# Circuit_Needs_aproval.net
KiCad netlist of a schematic drawn in EAGLE
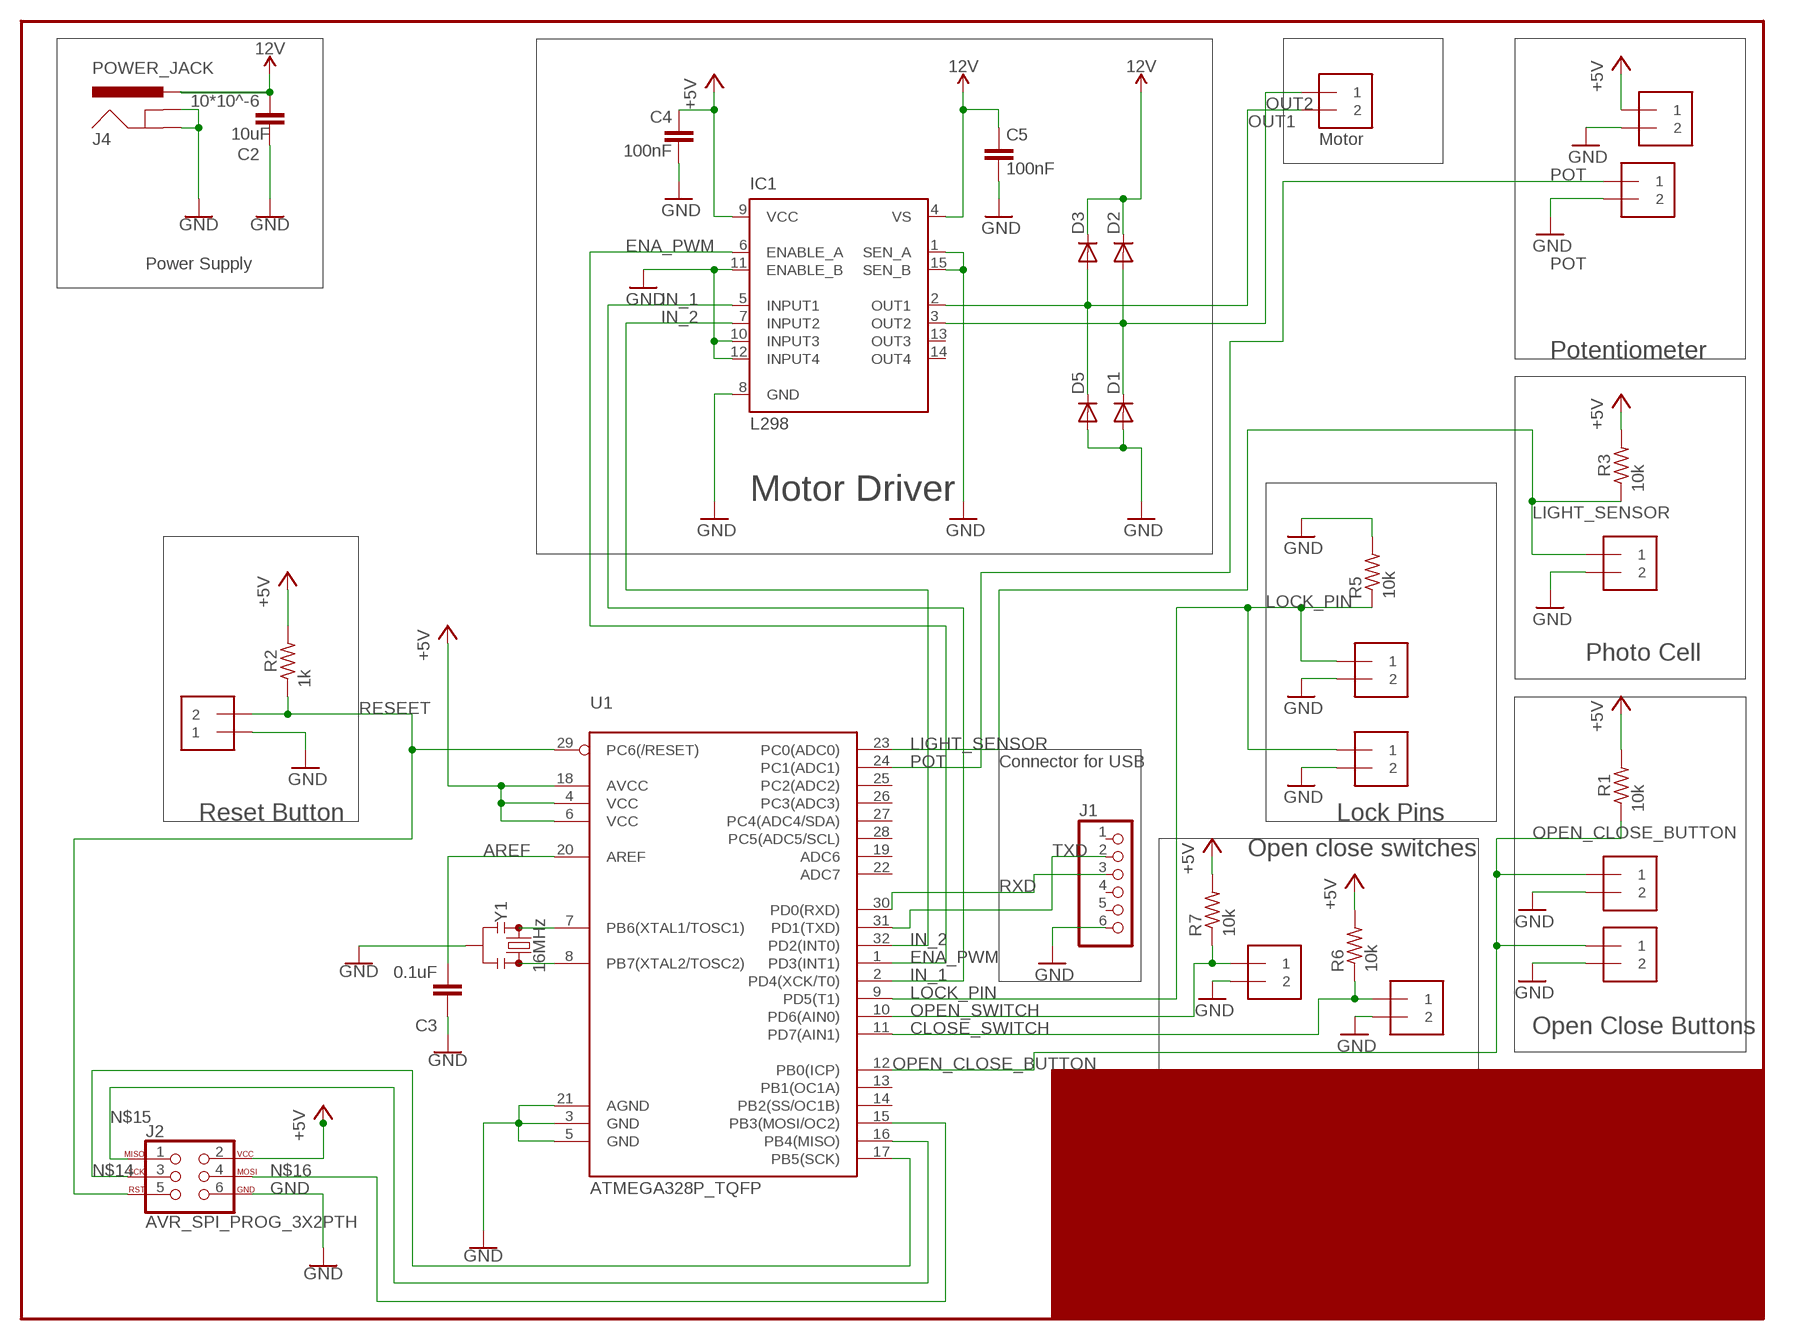
[diagram p0: schematic, sheet 1]

(export (version "E")
  (design (tool "Eeschema 10.0.6"))
  (components
    (comp (ref "C2")
      (value "10*10^-6")
      (footprint "eagle-import:C0805")
      (fields (field (name "SPICEPREFIX") "C") (field (name "SPICEPREFIX_1") "10uF"))
      (libsource (lib "eagle-import") (part "C-EUC0805"))
    )
    (comp (ref "C3")
      (value "0.1uF")
      (footprint "eagle-import:C0805")
      (libsource (lib "eagle-import") (part "C-EUC0805"))
    )
    (comp (ref "C4")
      (value "100nF")
      (footprint "eagle-import:C0805")
      (libsource (lib "eagle-import") (part "C-EUC0805"))
    )
    (comp (ref "C5")
      (value "100nF")
      (footprint "eagle-import:C0805")
      (libsource (lib "eagle-import") (part "C-EUC0805"))
    )
    (comp (ref "CLOSESWITCH")
      (value "1X2-3.5MM")
      (footprint "eagle-import:1X2-3.5MM")
      (libsource (lib "eagle-import") (part "1X2-3.5MM"))
    )
    (comp (ref "D1")
      (value "DIODE-DO214AA")
      (footprint "eagle-import:DO214AA")
      (libsource (lib "eagle-import") (part "DIODE-DO214AA"))
    )
    (comp (ref "D2")
      (value "DIODE-DO214AA")
      (footprint "eagle-import:DO214AA")
      (libsource (lib "eagle-import") (part "DIODE-DO214AA"))
    )
    (comp (ref "D3")
      (value "DIODE-DO214AA")
      (footprint "eagle-import:DO214AA")
      (libsource (lib "eagle-import") (part "DIODE-DO214AA"))
    )
    (comp (ref "D5")
      (value "DIODE-DO214AA")
      (footprint "eagle-import:DO214AA")
      (libsource (lib "eagle-import") (part "DIODE-DO214AA"))
    )
    (comp (ref "FRAME1")
      (value "FRAME-LETTER")
      (footprint "eagle-import:CREATIVE_COMMONS")
      (libsource (lib "eagle-import") (part "FRAME-LETTER"))
    )
    (comp (ref "IC1")
      (value "L298")
      (footprint "eagle-import:MULTIWATT-15")
      (fields (field (name "MPN") "L298N"))
      (libsource (lib "eagle-import") (part "L298"))
    )
    (comp (ref "INSIDE_BUTTON")
      (value "1X2-3.5MM")
      (footprint "eagle-import:1X2-3.5MM")
      (libsource (lib "eagle-import") (part "1X2-3.5MM"))
    )
    (comp (ref "J1")
      (value "PINHD-1X6")
      (footprint "eagle-import:1X06")
      (libsource (lib "eagle-import") (part "PINHD-1X6"))
    )
    (comp (ref "J2")
      (value "AVR_SPI_PROG_3X2PTH")
      (footprint "eagle-import:2X3")
      (libsource (lib "eagle-import") (part "AVR_SPI_PROG_3X2PTH"))
    )
    (comp (ref "J4")
      (value "POWER_JACK")
      (footprint "eagle-import:POWER_JACK_PTH")
      (libsource (lib "eagle-import") (part "POWER_JACK"))
    )
    (comp (ref "LIGHT_SENSOR")
      (value "1X2-3.5MM")
      (footprint "eagle-import:1X2-3.5MM")
      (libsource (lib "eagle-import") (part "1X2-3.5MM"))
    )
    (comp (ref "LOCK_PIN1")
      (value "1X2-3.5MM")
      (footprint "eagle-import:1X2-3.5MM")
      (libsource (lib "eagle-import") (part "1X2-3.5MM"))
    )
    (comp (ref "LOCK_PIN2")
      (value "1X2-3.5MM")
      (footprint "eagle-import:1X2-3.5MM")
      (libsource (lib "eagle-import") (part "1X2-3.5MM"))
    )
    (comp (ref "MOTOR")
      (value "1X2-3.5MM")
      (footprint "eagle-import:1X2-3.5MM")
      (libsource (lib "eagle-import") (part "1X2-3.5MM"))
    )
    (comp (ref "OUTSIDE_BUTTON")
      (value "1X2-3.5MM")
      (footprint "eagle-import:1X2-3.5MM")
      (libsource (lib "eagle-import") (part "1X2-3.5MM"))
    )
    (comp (ref "OUTSIDE_OPEN_BUTTON")
      (value "1X2-3.5MM")
      (footprint "eagle-import:1X2-3.5MM")
      (libsource (lib "eagle-import") (part "1X2-3.5MM"))
    )
    (comp (ref "POT")
      (value "1X2-3.5MM")
      (footprint "eagle-import:1X2-3.5MM")
      (libsource (lib "eagle-import") (part "1X2-3.5MM"))
    )
    (comp (ref "POTPOWER")
      (value "1X2-3.5MM")
      (footprint "eagle-import:1X2-3.5MM")
      (libsource (lib "eagle-import") (part "1X2-3.5MM"))
    )
    (comp (ref "R1")
      (value "10k")
      (footprint "eagle-import:M0805")
      (libsource (lib "eagle-import") (part "R-US_M0805"))
    )
    (comp (ref "R2")
      (value "1k")
      (footprint "eagle-import:M0805")
      (libsource (lib "eagle-import") (part "R-US_M0805"))
    )
    (comp (ref "R3")
      (value "10k")
      (footprint "eagle-import:M0805")
      (libsource (lib "eagle-import") (part "R-US_M0805"))
    )
    (comp (ref "R5")
      (value "10k")
      (footprint "eagle-import:M0805")
      (libsource (lib "eagle-import") (part "R-US_M0805"))
    )
    (comp (ref "R6")
      (value "10k")
      (footprint "eagle-import:M0805")
      (libsource (lib "eagle-import") (part "R-US_M0805"))
    )
    (comp (ref "R7")
      (value "10k")
      (footprint "eagle-import:M0805")
      (libsource (lib "eagle-import") (part "R-US_M0805"))
    )
    (comp (ref "RESETBUTTON")
      (value "1X2-3.5MM")
      (footprint "eagle-import:1X2-3.5MM")
      (libsource (lib "eagle-import") (part "1X2-3.5MM"))
    )
    (comp (ref "U1")
      (value "ATMEGA328P_TQFP")
      (footprint "eagle-import:TQFP32-08")
      (libsource (lib "eagle-import") (part "ATMEGA328P_TQFP"))
    )
    (comp (ref "Y1")
      (value "16MHz")
      (footprint "eagle-import:RESONATOR-SMD-3.2X1.3")
      (libsource (lib "eagle-import") (part "RESONATOR-16MHZSMD_3.2X1.3"))
    )
  )
  (nets
    (net (code "1") (name "+5V") (class "Default")
      (node (ref "C4") (pin "1") (pinfunction "1_1") (pintype "passive"))
      (node (ref "IC1") (pin "9") (pinfunction "VCC_9") (pintype "power_in"))
      (node (ref "J2") (pin "2") (pinfunction "2_2") (pintype "passive"))
      (node (ref "POTPOWER") (pin "1") (pinfunction "1_1") (pintype "passive"))
      (node (ref "R1") (pin "2") (pinfunction "2_2") (pintype "passive"))
      (node (ref "R2") (pin "2") (pinfunction "2_2") (pintype "passive"))
      (node (ref "R3") (pin "2") (pinfunction "2_2") (pintype "passive"))
      (node (ref "R6") (pin "2") (pinfunction "2_2") (pintype "passive"))
      (node (ref "R7") (pin "2") (pinfunction "2_2") (pintype "passive"))
      (node (ref "U1") (pin "18") (pinfunction "AVCC_18") (pintype "bidirectional"))
      (node (ref "U1") (pin "4") (pinfunction "VCC_4") (pintype "bidirectional"))
      (node (ref "U1") (pin "6") (pinfunction "VCC_6") (pintype "bidirectional"))
    )
    (net (code "2") (name "/AREF") (class "Default")
      (node (ref "C3") (pin "2") (pinfunction "2_2") (pintype "passive"))
      (node (ref "U1") (pin "20") (pinfunction "AREF_20") (pintype "bidirectional"))
    )
    (net (code "3") (name "/CLOSE_SWITCH") (class "Default")
      (node (ref "CLOSESWITCH") (pin "1") (pinfunction "1_1") (pintype "passive"))
      (node (ref "R6") (pin "1") (pinfunction "1_1") (pintype "passive"))
      (node (ref "U1") (pin "11") (pinfunction "PD7(AIN1)_11") (pintype "bidirectional"))
    )
    (net (code "4") (name "/ENA_PWM") (class "Default")
      (node (ref "IC1") (pin "6") (pinfunction "ENABLE_A_6") (pintype "input"))
      (node (ref "U1") (pin "1") (pinfunction "PD3(INT1)_1") (pintype "bidirectional"))
    )
    (net (code "5") (name "/IN_1") (class "Default")
      (node (ref "IC1") (pin "5") (pinfunction "INPUT1_5") (pintype "input"))
      (node (ref "U1") (pin "2") (pinfunction "PD4(XCK/T0)_2") (pintype "bidirectional"))
    )
    (net (code "6") (name "/IN_2") (class "Default")
      (node (ref "IC1") (pin "7") (pinfunction "INPUT2_7") (pintype "input"))
      (node (ref "U1") (pin "32") (pinfunction "PD2(INT0)_32") (pintype "bidirectional"))
    )
    (net (code "7") (name "/LIGHT_SENSOR") (class "Default")
      (node (ref "LIGHT_SENSOR") (pin "1") (pinfunction "1_1") (pintype "passive"))
      (node (ref "R3") (pin "1") (pinfunction "1_1") (pintype "passive"))
      (node (ref "U1") (pin "23") (pinfunction "PC0(ADC0)_23") (pintype "bidirectional"))
    )
    (net (code "8") (name "/LOCK_PIN") (class "Default")
      (node (ref "LOCK_PIN1") (pin "1") (pinfunction "1_1") (pintype "passive"))
      (node (ref "LOCK_PIN2") (pin "1") (pinfunction "1_1") (pintype "passive"))
      (node (ref "R5") (pin "1") (pinfunction "1_1") (pintype "passive"))
      (node (ref "U1") (pin "9") (pinfunction "PD5(T1)_9") (pintype "bidirectional"))
    )
    (net (code "9") (name "/N$14") (class "Default")
      (node (ref "J2") (pin "3") (pinfunction "3_3") (pintype "passive"))
      (node (ref "U1") (pin "17") (pinfunction "PB5(SCK)_17") (pintype "bidirectional"))
    )
    (net (code "10") (name "/N$15") (class "Default")
      (node (ref "J2") (pin "1") (pinfunction "1_1") (pintype "passive"))
      (node (ref "U1") (pin "16") (pinfunction "PB4(MISO)_16") (pintype "bidirectional"))
    )
    (net (code "11") (name "/N$16") (class "Default")
      (node (ref "J2") (pin "4") (pinfunction "4_4") (pintype "passive"))
      (node (ref "U1") (pin "15") (pinfunction "PB3(MOSI/OC2)_15") (pintype "bidirectional"))
    )
    (net (code "12") (name "/OPEN_CLOSE_BUTTON") (class "Default")
      (node (ref "INSIDE_BUTTON") (pin "1") (pinfunction "1_1") (pintype "passive"))
      (node (ref "OUTSIDE_BUTTON") (pin "1") (pinfunction "1_1") (pintype "passive"))
      (node (ref "R1") (pin "1") (pinfunction "1_1") (pintype "passive"))
      (node (ref "U1") (pin "12") (pinfunction "PB0(ICP)_12") (pintype "bidirectional"))
    )
    (net (code "13") (name "/OPEN_SWITCH") (class "Default")
      (node (ref "OUTSIDE_OPEN_BUTTON") (pin "1") (pinfunction "1_1") (pintype "passive"))
      (node (ref "R7") (pin "1") (pinfunction "1_1") (pintype "passive"))
      (node (ref "U1") (pin "10") (pinfunction "PD6(AIN0)_10") (pintype "bidirectional"))
    )
    (net (code "14") (name "/OUT1") (class "Default")
      (node (ref "D3") (pin "A") (pinfunction "A_A") (pintype "passive"))
      (node (ref "D5") (pin "C") (pinfunction "C_C") (pintype "passive"))
      (node (ref "IC1") (pin "2") (pinfunction "OUT1_2") (pintype "output"))
      (node (ref "MOTOR") (pin "2") (pinfunction "2_2") (pintype "passive"))
    )
    (net (code "15") (name "/OUT2") (class "Default")
      (node (ref "D1") (pin "C") (pinfunction "C_C") (pintype "passive"))
      (node (ref "D2") (pin "A") (pinfunction "A_A") (pintype "passive"))
      (node (ref "IC1") (pin "3") (pinfunction "OUT2_3") (pintype "output"))
      (node (ref "MOTOR") (pin "1") (pinfunction "1_1") (pintype "passive"))
    )
    (net (code "16") (name "/POT") (class "Default")
      (node (ref "POT") (pin "1") (pinfunction "1_1") (pintype "passive"))
      (node (ref "U1") (pin "24") (pinfunction "PC1(ADC1)_24") (pintype "bidirectional"))
    )
    (net (code "17") (name "/RESEET") (class "Default")
      (node (ref "J2") (pin "5") (pinfunction "5_5") (pintype "passive"))
      (node (ref "R2") (pin "1") (pinfunction "1_1") (pintype "passive"))
      (node (ref "RESETBUTTON") (pin "2") (pinfunction "2_2") (pintype "passive"))
      (node (ref "U1") (pin "29") (pinfunction "PC6(/RESET)_29") (pintype "bidirectional"))
    )
    (net (code "18") (name "/RXD") (class "Default")
      (node (ref "J1") (pin "3") (pinfunction "3_3") (pintype "passive"))
      (node (ref "U1") (pin "30") (pinfunction "PD0(RXD)_30") (pintype "bidirectional"))
    )
    (net (code "19") (name "/TXD") (class "Default")
      (node (ref "J1") (pin "2") (pinfunction "2_2") (pintype "passive"))
      (node (ref "U1") (pin "31") (pinfunction "PD1(TXD)_31") (pintype "bidirectional"))
    )
    (net (code "20") (name "12V") (class "Default")
      (node (ref "C2") (pin "2") (pinfunction "2_2") (pintype "passive"))
      (node (ref "C5") (pin "1") (pinfunction "1_1") (pintype "passive"))
      (node (ref "D2") (pin "C") (pinfunction "C_C") (pintype "passive"))
      (node (ref "D3") (pin "C") (pinfunction "C_C") (pintype "passive"))
      (node (ref "IC1") (pin "4") (pinfunction "VS_4") (pintype "power_in"))
      (node (ref "J4") (pin "PWR") (pinfunction "PWR_PWR") (pintype "bidirectional"))
    )
    (net (code "21") (name "GND") (class "Default")
      (node (ref "C2") (pin "1") (pinfunction "1_1") (pintype "passive"))
      (node (ref "C3") (pin "1") (pinfunction "1_1") (pintype "passive"))
      (node (ref "C4") (pin "2") (pinfunction "2_2") (pintype "passive"))
      (node (ref "C5") (pin "2") (pinfunction "2_2") (pintype "passive"))
      (node (ref "CLOSESWITCH") (pin "2") (pinfunction "2_2") (pintype "passive"))
      (node (ref "D1") (pin "A") (pinfunction "A_A") (pintype "passive"))
      (node (ref "D5") (pin "A") (pinfunction "A_A") (pintype "passive"))
      (node (ref "IC1") (pin "1") (pinfunction "SEN_A_1") (pintype "input"))
      (node (ref "IC1") (pin "10") (pinfunction "INPUT3_10") (pintype "input"))
      (node (ref "IC1") (pin "11") (pinfunction "ENABLE_B_11") (pintype "input"))
      (node (ref "IC1") (pin "12") (pinfunction "INPUT4_12") (pintype "input"))
      (node (ref "IC1") (pin "15") (pinfunction "SEN_B_15") (pintype "input"))
      (node (ref "IC1") (pin "8") (pinfunction "GND_8") (pintype "power_in"))
      (node (ref "INSIDE_BUTTON") (pin "2") (pinfunction "2_2") (pintype "passive"))
      (node (ref "J1") (pin "6") (pinfunction "6_6") (pintype "passive"))
      (node (ref "J2") (pin "6") (pinfunction "6_6") (pintype "passive"))
      (node (ref "J4") (pin "GND") (pinfunction "GND_GND") (pintype "bidirectional"))
      (node (ref "J4") (pin "GNDBREAK") (pinfunction "GNDBREAK_GNDBREAK") (pintype "bidirectional"))
      (node (ref "LIGHT_SENSOR") (pin "2") (pinfunction "2_2") (pintype "passive"))
      (node (ref "LOCK_PIN1") (pin "2") (pinfunction "2_2") (pintype "passive"))
      (node (ref "LOCK_PIN2") (pin "2") (pinfunction "2_2") (pintype "passive"))
      (node (ref "OUTSIDE_BUTTON") (pin "2") (pinfunction "2_2") (pintype "passive"))
      (node (ref "OUTSIDE_OPEN_BUTTON") (pin "2") (pinfunction "2_2") (pintype "passive"))
      (node (ref "POT") (pin "2") (pinfunction "2_2") (pintype "passive"))
      (node (ref "POTPOWER") (pin "2") (pinfunction "2_2") (pintype "passive"))
      (node (ref "R5") (pin "2") (pinfunction "2_2") (pintype "passive"))
      (node (ref "RESETBUTTON") (pin "1") (pinfunction "1_1") (pintype "passive"))
      (node (ref "U1") (pin "21") (pinfunction "AGND_21") (pintype "bidirectional"))
      (node (ref "U1") (pin "3") (pinfunction "GND_3") (pintype "bidirectional"))
      (node (ref "U1") (pin "5") (pinfunction "GND_5") (pintype "bidirectional"))
      (node (ref "Y1") (pin "2") (pinfunction "2_2") (pintype "passive"))
    )
    (net (code "22") (name "Net-(U1-PB6(XTAL1{slash}TOSC1))") (class "Default")
      (node (ref "U1") (pin "7") (pinfunction "PB6(XTAL1/TOSC1)_7") (pintype "bidirectional"))
      (node (ref "Y1") (pin "1") (pinfunction "1_1") (pintype "passive"))
    )
    (net (code "23") (name "Net-(U1-PB7(XTAL2{slash}TOSC2))") (class "Default")
      (node (ref "U1") (pin "8") (pinfunction "PB7(XTAL2/TOSC2)_8") (pintype "bidirectional"))
      (node (ref "Y1") (pin "3") (pinfunction "3_3") (pintype "passive"))
    )
    (net (code "24") (name "unconnected-(IC1-OUT3-Pad13)") (class "Default")
      (node (ref "IC1") (pin "13") (pinfunction "OUT3_13") (pintype "output"))
    )
    (net (code "25") (name "unconnected-(IC1-OUT4-Pad14)") (class "Default")
      (node (ref "IC1") (pin "14") (pinfunction "OUT4_14") (pintype "output"))
    )
    (net (code "26") (name "unconnected-(J1-Pad1)") (class "Default")
      (node (ref "J1") (pin "1") (pinfunction "1_1") (pintype "passive"))
    )
    (net (code "27") (name "unconnected-(J1-Pad4)") (class "Default")
      (node (ref "J1") (pin "4") (pinfunction "4_4") (pintype "passive"))
    )
    (net (code "28") (name "unconnected-(J1-Pad5)") (class "Default")
      (node (ref "J1") (pin "5") (pinfunction "5_5") (pintype "passive"))
    )
    (net (code "29") (name "unconnected-(U1-ADC6-Pad19)") (class "Default")
      (node (ref "U1") (pin "19") (pinfunction "ADC6_19") (pintype "bidirectional"))
    )
    (net (code "30") (name "unconnected-(U1-ADC7-Pad22)") (class "Default")
      (node (ref "U1") (pin "22") (pinfunction "ADC7_22") (pintype "bidirectional"))
    )
    (net (code "31") (name "unconnected-(U1-PB1(OC1A)-Pad13)") (class "Default")
      (node (ref "U1") (pin "13") (pinfunction "PB1(OC1A)_13") (pintype "bidirectional"))
    )
    (net (code "32") (name "unconnected-(U1-PB2(SS{slash}OC1B)-Pad14)") (class "Default")
      (node (ref "U1") (pin "14") (pinfunction "PB2(SS/OC1B)_14") (pintype "bidirectional"))
    )
    (net (code "33") (name "unconnected-(U1-PC2(ADC2)-Pad25)") (class "Default")
      (node (ref "U1") (pin "25") (pinfunction "PC2(ADC2)_25") (pintype "bidirectional"))
    )
    (net (code "34") (name "unconnected-(U1-PC3(ADC3)-Pad26)") (class "Default")
      (node (ref "U1") (pin "26") (pinfunction "PC3(ADC3)_26") (pintype "bidirectional"))
    )
    (net (code "35") (name "unconnected-(U1-PC4(ADC4{slash}SDA)-Pad27)") (class "Default")
      (node (ref "U1") (pin "27") (pinfunction "PC4(ADC4/SDA)_27") (pintype "bidirectional"))
    )
    (net (code "36") (name "unconnected-(U1-PC5(ADC5{slash}SCL)-Pad28)") (class "Default")
      (node (ref "U1") (pin "28") (pinfunction "PC5(ADC5/SCL)_28") (pintype "bidirectional"))
    )
  )
)
